# IOB-Adapter-Turtle.net
KiCad netlist of a schematic drawn in EAGLE
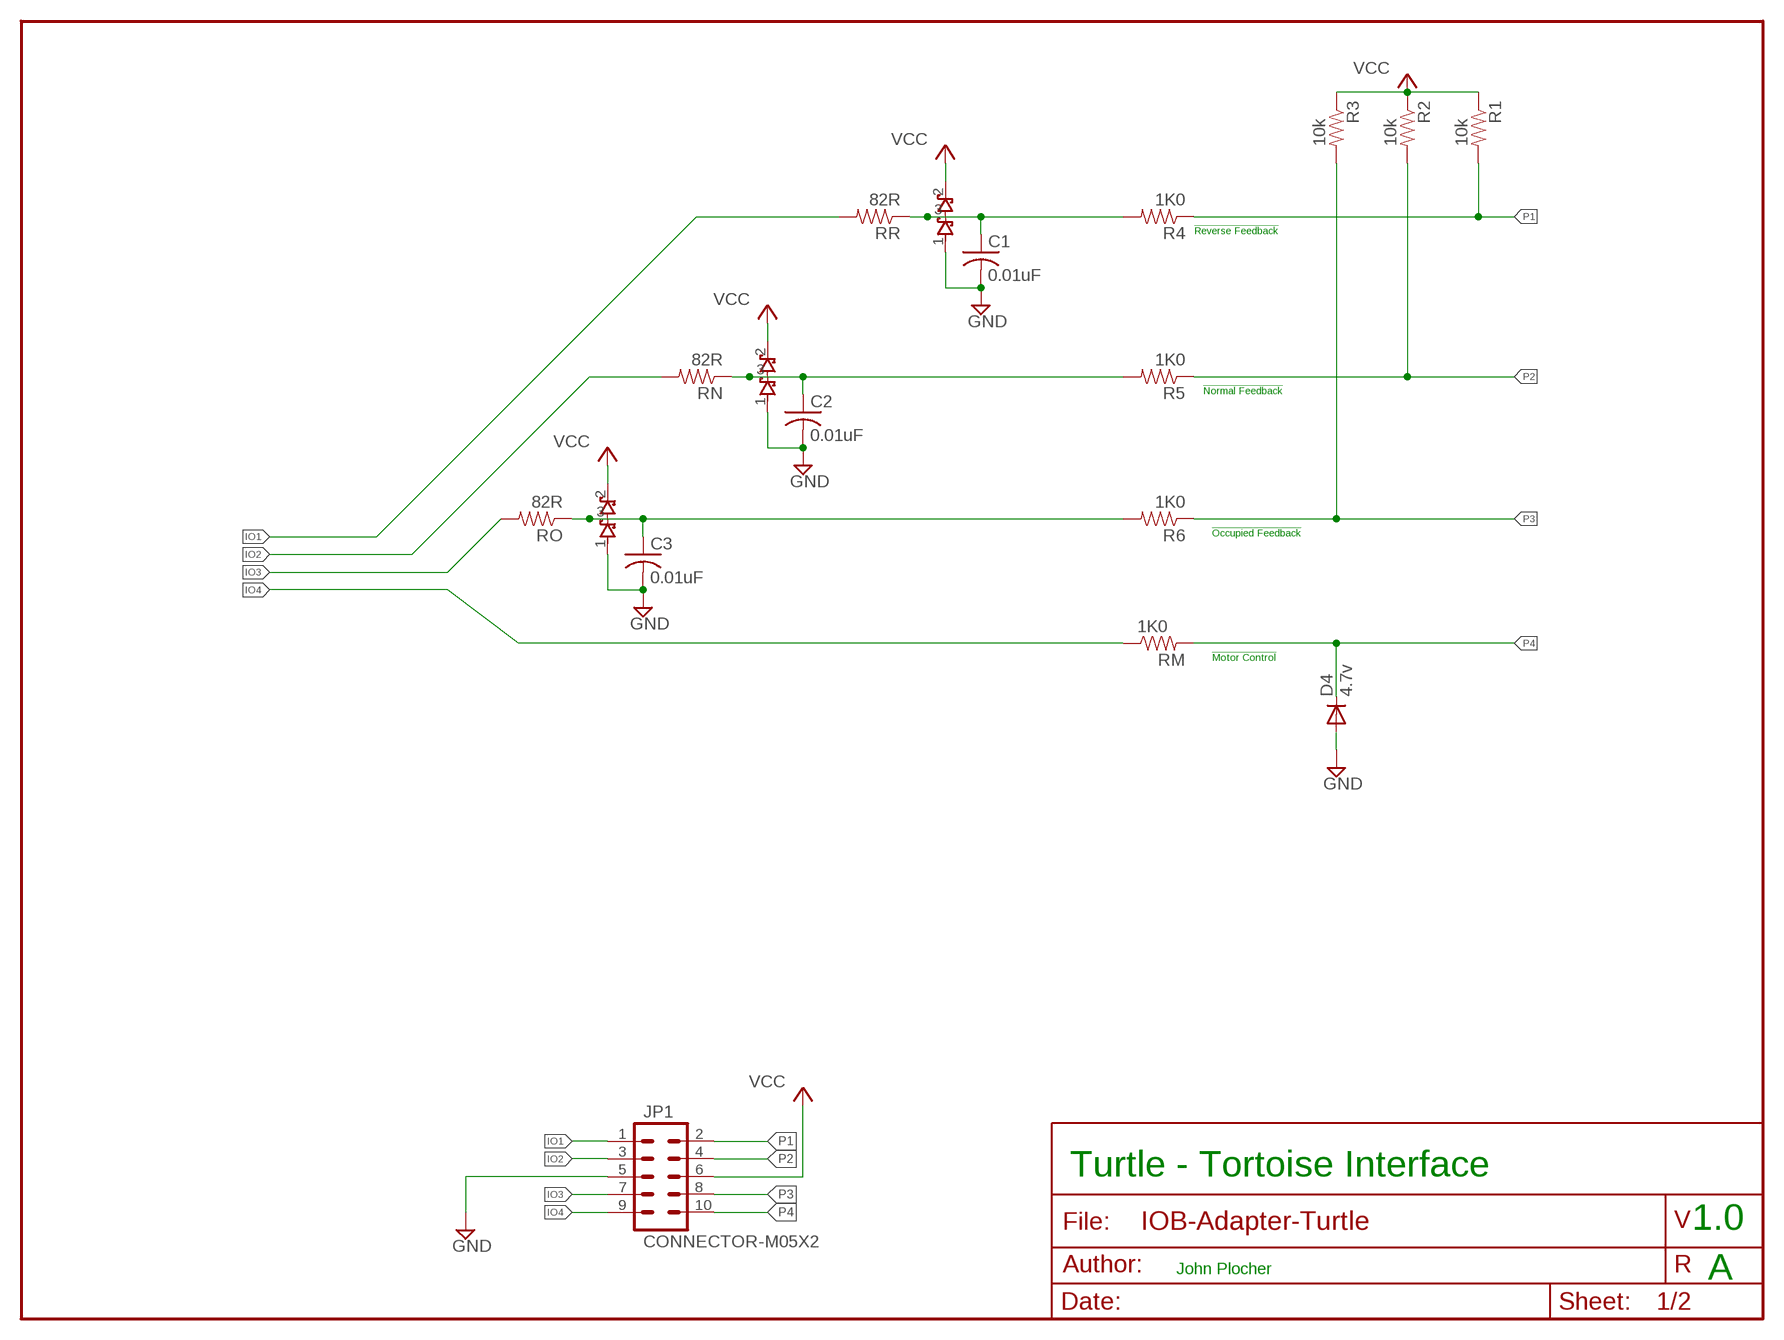
[diagram p0: schematic, sheet 1]
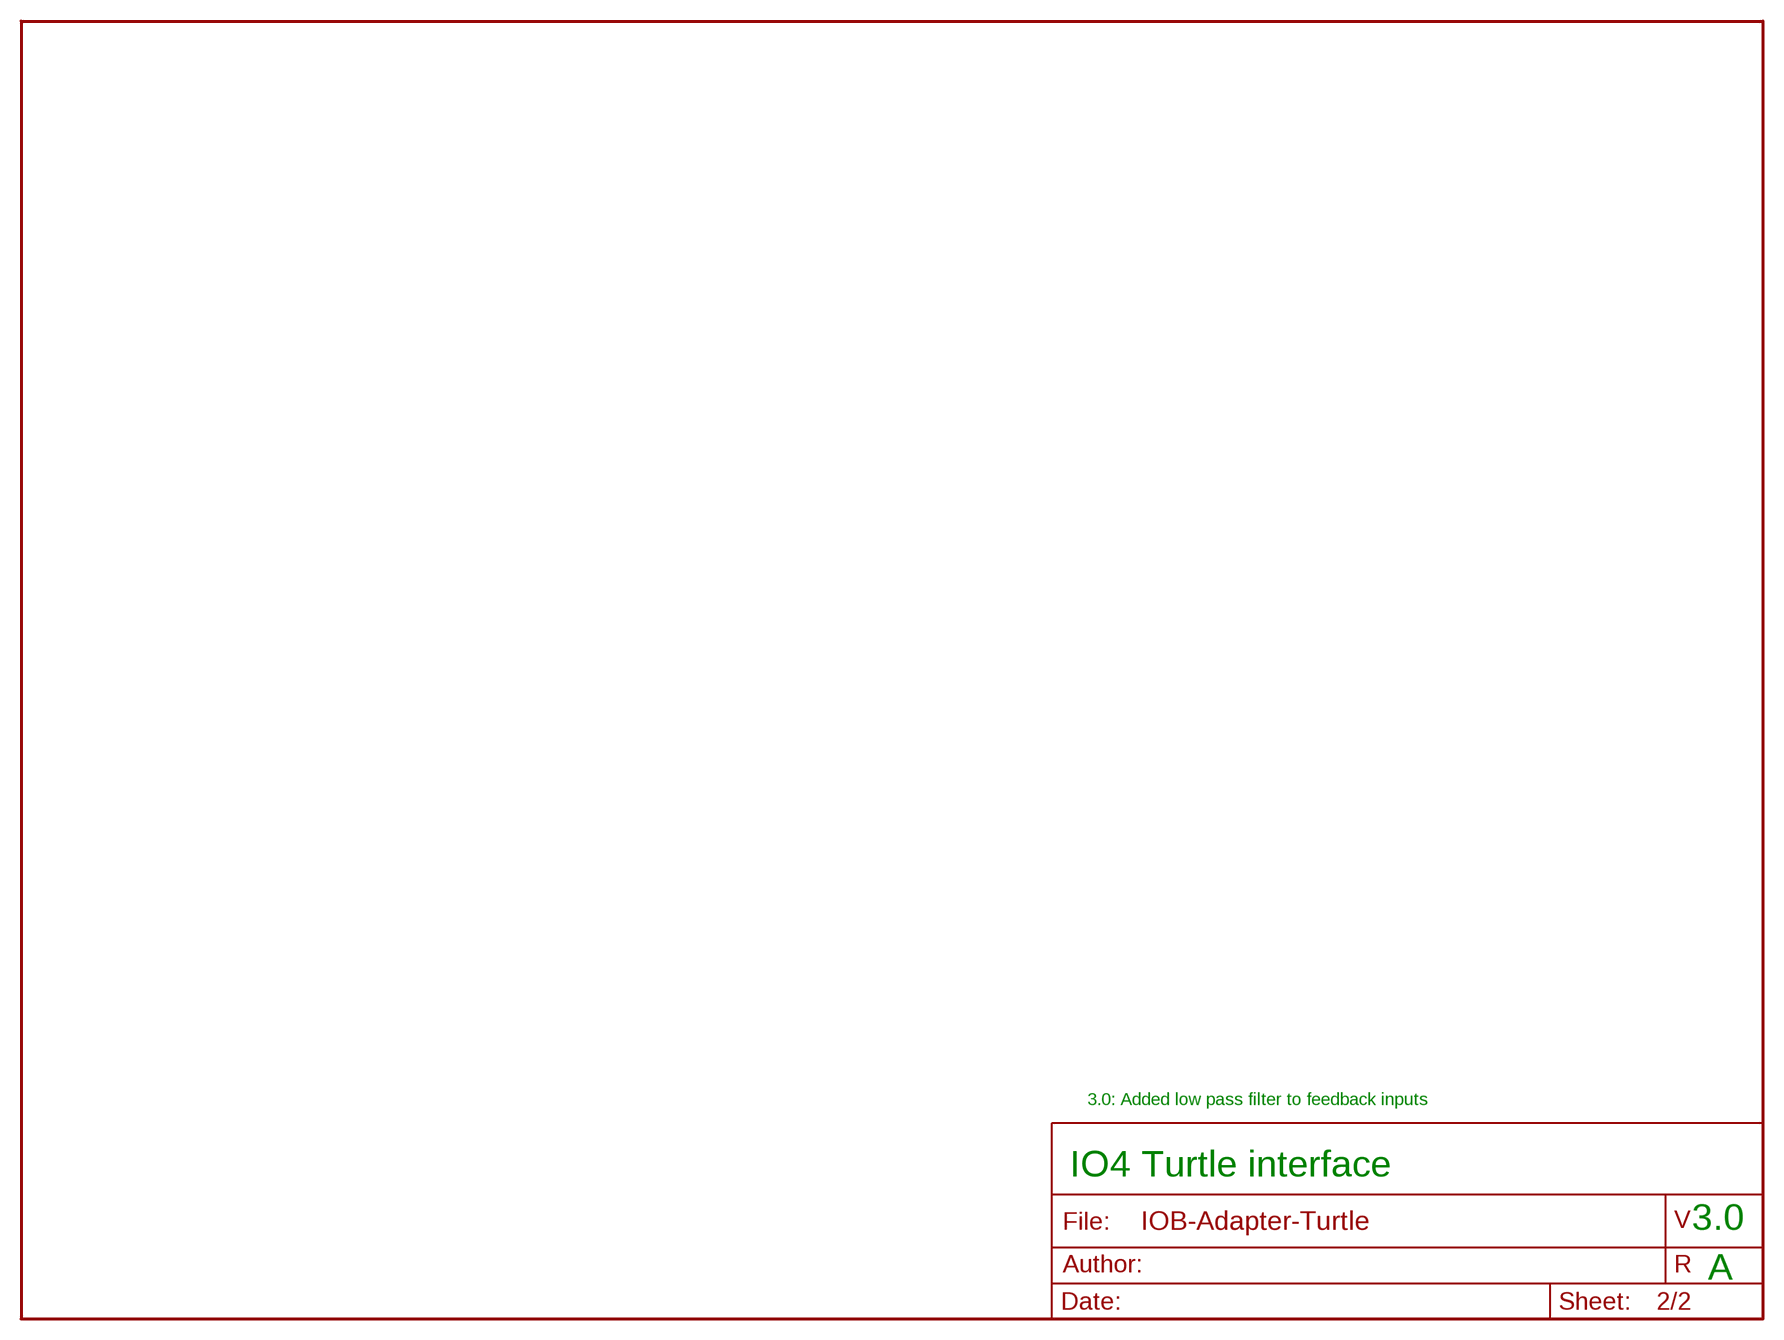
[diagram p1: schematic, sheet 2]

(export (version "E")
  (design (tool "Eeschema 10.0.6"))
  (components
    (comp (ref "C1")
      (value "0.01uF")
      (footprint "eagle-import:0603-CAP")
      (libsource (lib "eagle-import") (part "CAP0603"))
    )
    (comp (ref "C2")
      (value "0.01uF")
      (footprint "eagle-import:0603-CAP")
      (libsource (lib "eagle-import") (part "CAP0603"))
    )
    (comp (ref "C3")
      (value "0.01uF")
      (footprint "eagle-import:0603-CAP")
      (libsource (lib "eagle-import") (part "CAP0603"))
    )
    (comp (ref "D1")
      (value "BAT54S")
      (footprint "eagle-import:SOT23")
      (libsource (lib "eagle-import") (part "DIODE-BAT54S23"))
    )
    (comp (ref "D2")
      (value "BAT54S")
      (footprint "eagle-import:SOT23")
      (libsource (lib "eagle-import") (part "DIODE-BAT54S23"))
    )
    (comp (ref "D3")
      (value "BAT54S")
      (footprint "eagle-import:SOT23")
      (libsource (lib "eagle-import") (part "DIODE-BAT54S23"))
    )
    (comp (ref "D4")
      (value "4.7v")
      (footprint "eagle-import:SOT23")
      (libsource (lib "eagle-import") (part "DIODESOT23"))
    )
    (comp (ref "JP1")
      (value "CONNECTOR-M05X2")
      (footprint "eagle-import:IOB-V3-MODULE")
      (libsource (lib "eagle-import") (part "CONNECTOR-M05X2"))
    )
    (comp (ref "R1")
      (value "10k")
      (footprint "eagle-import:0805-RES")
      (libsource (lib "eagle-import") (part "R0805-RES"))
    )
    (comp (ref "R2")
      (value "10k")
      (footprint "eagle-import:0805-RES")
      (libsource (lib "eagle-import") (part "R0805-RES"))
    )
    (comp (ref "R3")
      (value "10k")
      (footprint "eagle-import:0805-RES")
      (libsource (lib "eagle-import") (part "R0805-RES"))
    )
    (comp (ref "R4")
      (value "1K0")
      (footprint "eagle-import:0603-RES")
      (libsource (lib "eagle-import") (part "R0603-RES"))
    )
    (comp (ref "R5")
      (value "1K0")
      (footprint "eagle-import:0603-RES")
      (libsource (lib "eagle-import") (part "R0603-RES"))
    )
    (comp (ref "R6")
      (value "1K0")
      (footprint "eagle-import:0603-RES")
      (libsource (lib "eagle-import") (part "R0603-RES"))
    )
    (comp (ref "RM")
      (value "1K0")
      (footprint "eagle-import:0603-RES")
      (libsource (lib "eagle-import") (part "R0603-RES"))
    )
    (comp (ref "RN")
      (value "82R")
      (footprint "eagle-import:0805-RES")
      (libsource (lib "eagle-import") (part "R0805-RES"))
    )
    (comp (ref "RO")
      (value "82R")
      (footprint "eagle-import:0805-RES")
      (libsource (lib "eagle-import") (part "R0805-RES"))
    )
    (comp (ref "RR")
      (value "82R")
      (footprint "eagle-import:0805-RES")
      (libsource (lib "eagle-import") (part "R0805-RES"))
    )
  )
  (nets
    (net (code "1") (name "GND") (class "Default")
      (node (ref "C1") (pin "2") (pinfunction "2_2") (pintype "passive"))
      (node (ref "C2") (pin "2") (pinfunction "2_2") (pintype "passive"))
      (node (ref "C3") (pin "2") (pinfunction "2_2") (pintype "passive"))
      (node (ref "D1") (pin "1") (pinfunction "A1_1") (pintype "bidirectional"))
      (node (ref "D2") (pin "1") (pinfunction "A1_1") (pintype "bidirectional"))
      (node (ref "D3") (pin "1") (pinfunction "A1_1") (pintype "bidirectional"))
      (node (ref "D4") (pin "1") (pinfunction "A_1") (pintype "passive"))
      (node (ref "JP1") (pin "5") (pinfunction "5_5") (pintype "passive"))
    )
    (net (code "2") (name "IO1") (class "Default")
      (node (ref "JP1") (pin "1") (pinfunction "1_1") (pintype "passive"))
      (node (ref "RR") (pin "2") (pinfunction "2_2") (pintype "passive"))
    )
    (net (code "3") (name "IO2") (class "Default")
      (node (ref "JP1") (pin "3") (pinfunction "3_3") (pintype "passive"))
      (node (ref "RN") (pin "2") (pinfunction "2_2") (pintype "passive"))
    )
    (net (code "4") (name "IO3") (class "Default")
      (node (ref "JP1") (pin "7") (pinfunction "7_7") (pintype "passive"))
      (node (ref "RO") (pin "2") (pinfunction "2_2") (pintype "passive"))
    )
    (net (code "5") (name "IO4") (class "Default")
      (node (ref "JP1") (pin "9") (pinfunction "9_9") (pintype "passive"))
      (node (ref "RM") (pin "1") (pinfunction "1_1") (pintype "passive"))
    )
    (net (code "6") (name "Net-(D1-COM)") (class "Default")
      (node (ref "C1") (pin "1") (pinfunction "1_1") (pintype "passive"))
      (node (ref "D1") (pin "3") (pinfunction "COM_3") (pintype "bidirectional"))
      (node (ref "R4") (pin "2") (pinfunction "2_2") (pintype "passive"))
      (node (ref "RR") (pin "1") (pinfunction "1_1") (pintype "passive"))
    )
    (net (code "7") (name "Net-(D2-COM)") (class "Default")
      (node (ref "C2") (pin "1") (pinfunction "1_1") (pintype "passive"))
      (node (ref "D2") (pin "3") (pinfunction "COM_3") (pintype "bidirectional"))
      (node (ref "R5") (pin "2") (pinfunction "2_2") (pintype "passive"))
      (node (ref "RN") (pin "1") (pinfunction "1_1") (pintype "passive"))
    )
    (net (code "8") (name "Net-(D3-COM)") (class "Default")
      (node (ref "C3") (pin "1") (pinfunction "1_1") (pintype "passive"))
      (node (ref "D3") (pin "3") (pinfunction "COM_3") (pintype "bidirectional"))
      (node (ref "R6") (pin "2") (pinfunction "2_2") (pintype "passive"))
      (node (ref "RO") (pin "1") (pinfunction "1_1") (pintype "passive"))
    )
    (net (code "9") (name "P1") (class "Default")
      (node (ref "JP1") (pin "2") (pinfunction "2_2") (pintype "passive"))
      (node (ref "R1") (pin "2") (pinfunction "2_2") (pintype "passive"))
      (node (ref "R4") (pin "1") (pinfunction "1_1") (pintype "passive"))
    )
    (net (code "10") (name "P2") (class "Default")
      (node (ref "JP1") (pin "4") (pinfunction "4_4") (pintype "passive"))
      (node (ref "R2") (pin "2") (pinfunction "2_2") (pintype "passive"))
      (node (ref "R5") (pin "1") (pinfunction "1_1") (pintype "passive"))
    )
    (net (code "11") (name "P3") (class "Default")
      (node (ref "JP1") (pin "8") (pinfunction "8_8") (pintype "passive"))
      (node (ref "R3") (pin "2") (pinfunction "2_2") (pintype "passive"))
      (node (ref "R6") (pin "1") (pinfunction "1_1") (pintype "passive"))
    )
    (net (code "12") (name "P4") (class "Default")
      (node (ref "D4") (pin "3") (pinfunction "C_3") (pintype "passive"))
      (node (ref "JP1") (pin "10") (pinfunction "10_10") (pintype "passive"))
      (node (ref "RM") (pin "2") (pinfunction "2_2") (pintype "passive"))
    )
    (net (code "13") (name "VCC") (class "Default")
      (node (ref "D1") (pin "2") (pinfunction "C2_2") (pintype "bidirectional"))
      (node (ref "D2") (pin "2") (pinfunction "C2_2") (pintype "bidirectional"))
      (node (ref "D3") (pin "2") (pinfunction "C2_2") (pintype "bidirectional"))
      (node (ref "JP1") (pin "6") (pinfunction "6_6") (pintype "passive"))
      (node (ref "R1") (pin "1") (pinfunction "1_1") (pintype "passive"))
      (node (ref "R2") (pin "1") (pinfunction "1_1") (pintype "passive"))
      (node (ref "R3") (pin "1") (pinfunction "1_1") (pintype "passive"))
    )
  )
)
